# dac.net
KiCad netlist of a schematic drawn in Altium Designer
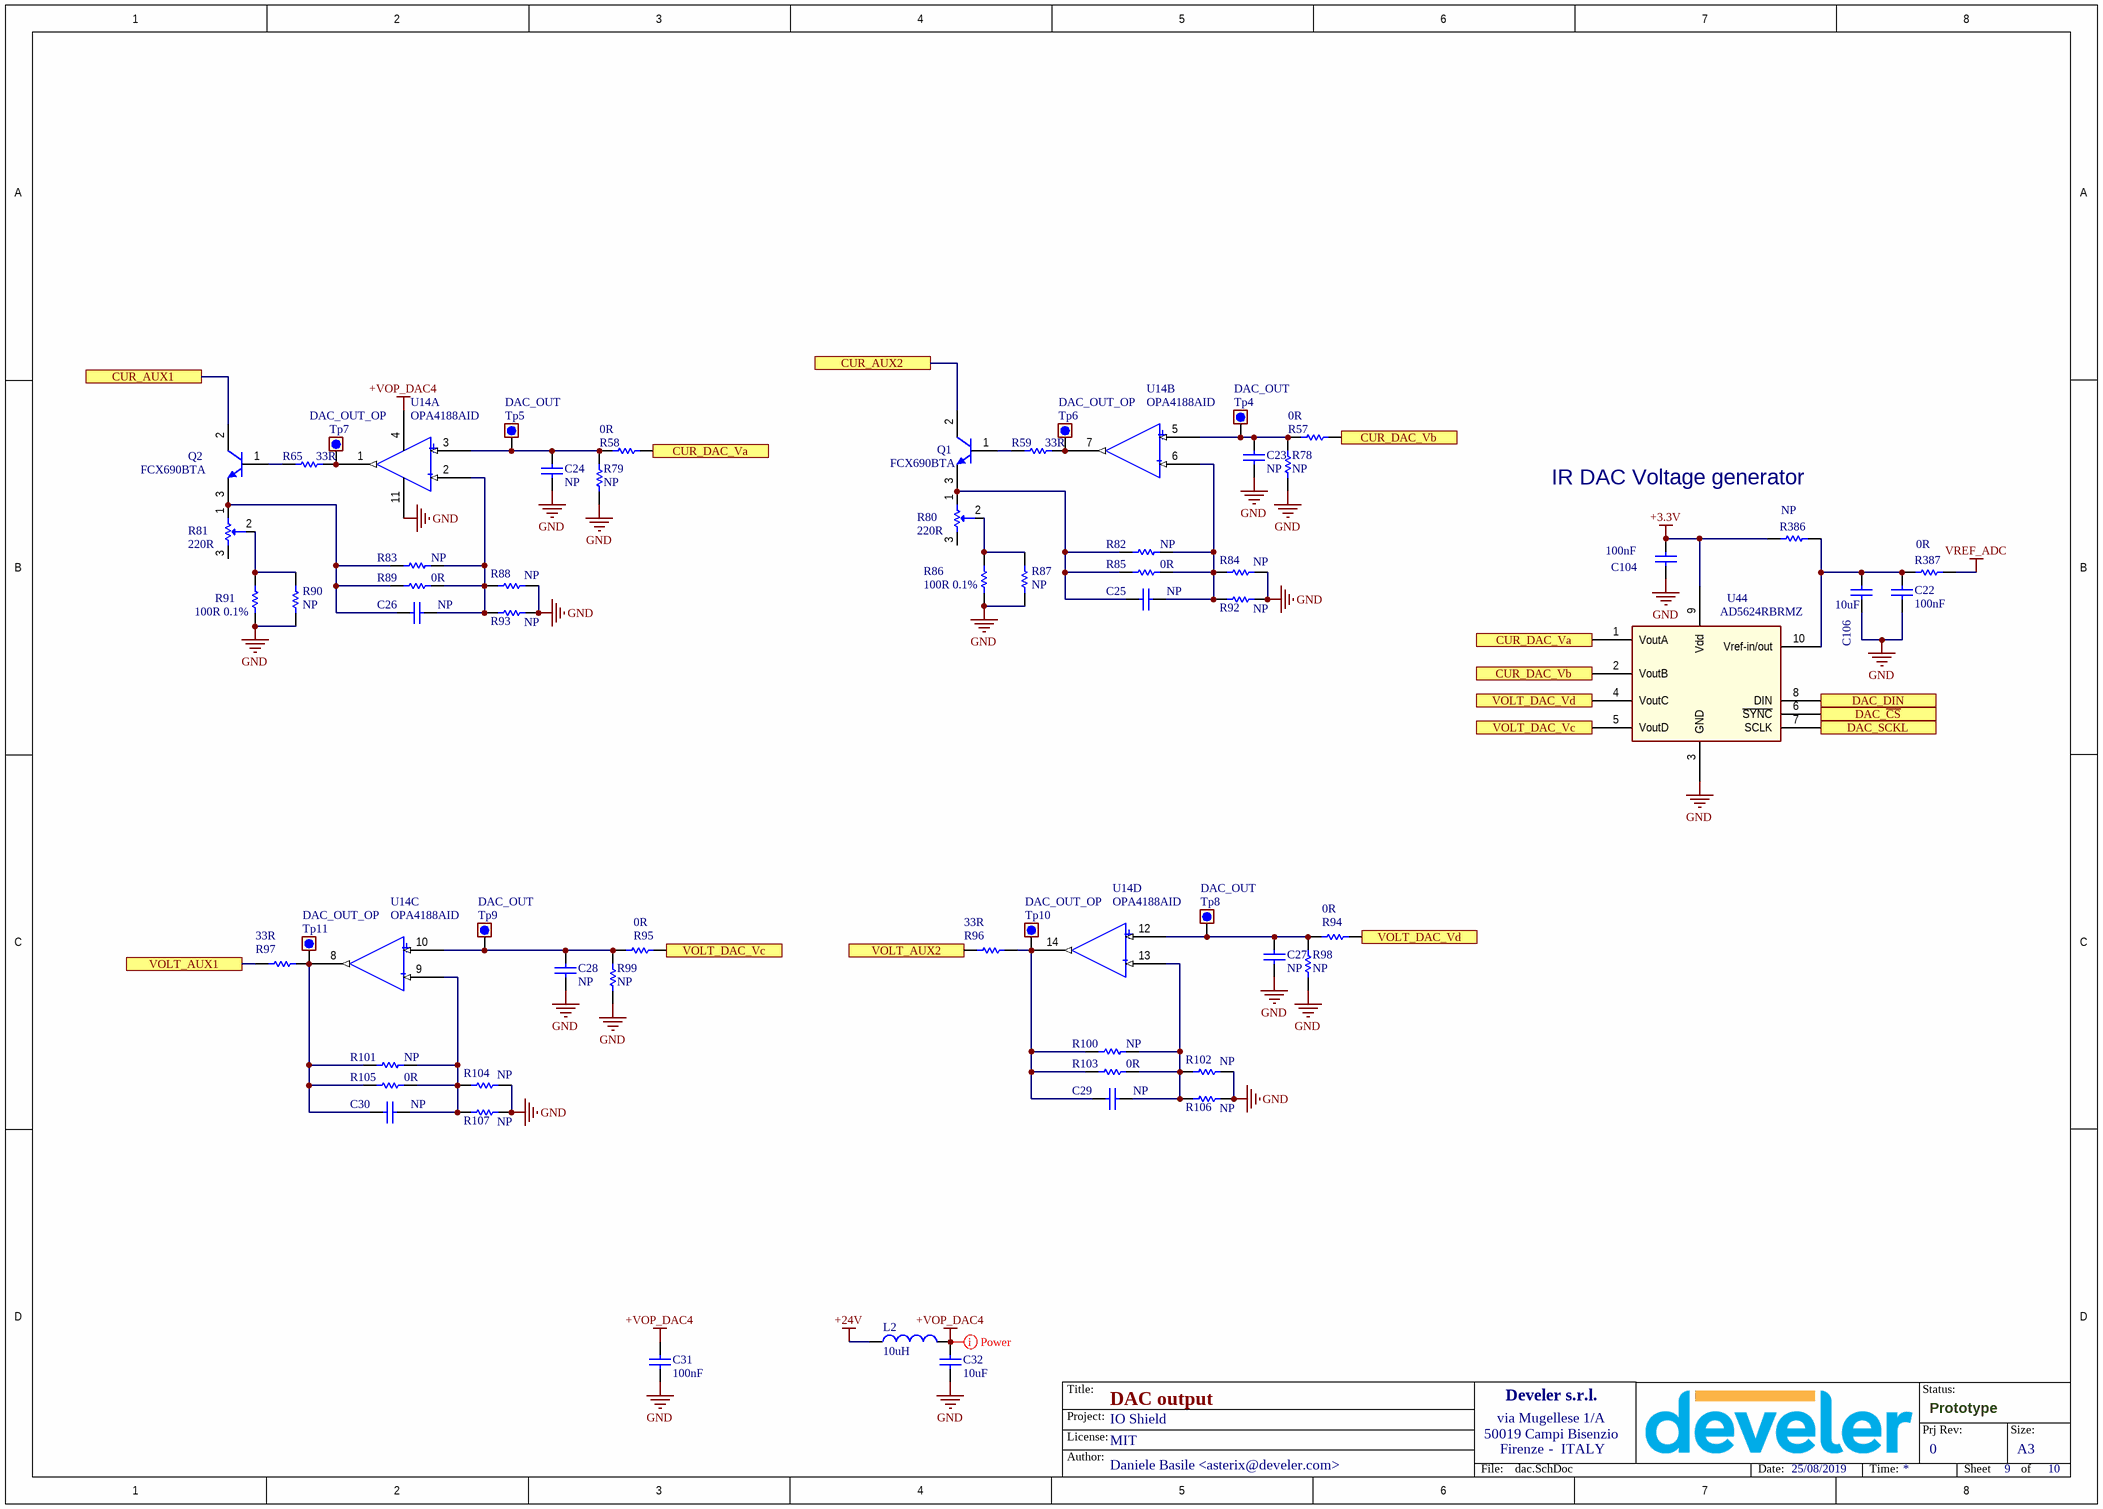
[diagram p0: dac.SchDoc]

(export (version "E")
  (design (tool "Eeschema 10.0.6"))
  (components
    (comp (ref "C22")
      (value "100nF")
      (footprint "0603_[1608]")
      (description "Ceramic X7R 50V")
      (fields (field (name "PUBLISHER") "Altium Limited"))
      (libsource (lib "DEVELER_Library") (part "Cap"))
    )
    (comp (ref "C23")
      (value "NP")
      (footprint "0603_[1608]")
      (description "Ceramic X7R 50V")
      (fields (field (name "PUBLISHER") "Altium Limited"))
      (libsource (lib "DEVELER_Library") (part "Cap"))
    )
    (comp (ref "C24")
      (value "NP")
      (footprint "0603_[1608]")
      (description "Ceramic X7R 50V")
      (fields (field (name "PUBLISHER") "Altium Limited"))
      (libsource (lib "DEVELER_Library") (part "Cap"))
    )
    (comp (ref "C25")
      (value "NP")
      (footprint "0603_[1608]")
      (description "Ceramic X7R 50V")
      (fields (field (name "PUBLISHER") "Altium Limited"))
      (libsource (lib "DEVELER_Library") (part "Cap"))
    )
    (comp (ref "C26")
      (value "NP")
      (footprint "0603_[1608]")
      (description "Ceramic X7R 50V")
      (fields (field (name "PUBLISHER") "Altium Limited"))
      (libsource (lib "DEVELER_Library") (part "Cap"))
    )
    (comp (ref "C27")
      (value "NP")
      (footprint "0603_[1608]")
      (description "Ceramic X7R 50V")
      (fields (field (name "PUBLISHER") "Altium Limited"))
      (libsource (lib "DEVELER_Library") (part "Cap"))
    )
    (comp (ref "C28")
      (value "NP")
      (footprint "0603_[1608]")
      (description "Ceramic X7R 50V")
      (fields (field (name "PUBLISHER") "Altium Limited"))
      (libsource (lib "DEVELER_Library") (part "Cap"))
    )
    (comp (ref "C29")
      (value "NP")
      (footprint "0603_[1608]")
      (description "Ceramic X7R 50V")
      (fields (field (name "PUBLISHER") "Altium Limited"))
      (libsource (lib "DEVELER_Library") (part "Cap"))
    )
    (comp (ref "C30")
      (value "NP")
      (footprint "0603_[1608]")
      (description "Ceramic X7R 50V")
      (fields (field (name "PUBLISHER") "Altium Limited"))
      (libsource (lib "DEVELER_Library") (part "Cap"))
    )
    (comp (ref "C31")
      (value "100nF")
      (footprint "0603_[1608]")
      (description "Ceramic X7R 50V")
      (fields (field (name "PUBLISHER") "Altium Limited"))
      (libsource (lib "DEVELER_Library") (part "Cap"))
    )
    (comp (ref "C32")
      (value "10uF")
      (footprint "1206_[3216]")
      (description "Ceramic X7R 25V")
      (fields (field (name "PUBLISHER") "Altium Limited"))
      (libsource (lib "DEVELER_Library") (part "Cap"))
    )
    (comp (ref "C104")
      (value "100nF")
      (footprint "0603_[1608]")
      (description "Ceramic X7R 50V")
      (fields (field (name "PUBLISHER") "Altium Limited"))
      (libsource (lib "DEVELER_Library") (part "Cap"))
    )
    (comp (ref "C106")
      (value "10uF")
      (footprint "1206_[3216]")
      (description "Ceramic X7R 25V")
      (fields (field (name "PUBLISHER") "Altium Limited"))
      (libsource (lib "DEVELER_Library") (part "Cap"))
    )
    (comp (ref "L2")
      (value "10uH")
      (footprint "1210_[3225]")
      (description "INDUCTOR, 1210 CASE, 10.0UH (ELJPA100KF)")
      (fields (field (name "PUBLISHER") "Altium Limited"))
      (libsource (lib "DEVELER_Library") (part "Inductor"))
    )
    (comp (ref "Q1")
      (value "FCX690BTA")
      (footprint "SOT-89")
      (description "NPN Bipolar Transistor")
      (fields (field (name "PUBLISHER") "Altium Limited"))
      (libsource (lib "Miscellaneous Devices") (part "NPN"))
    )
    (comp (ref "Q2")
      (value "FCX690BTA")
      (footprint "SOT-89")
      (description "NPN Bipolar Transistor")
      (fields (field (name "PUBLISHER") "Altium Limited"))
      (libsource (lib "Miscellaneous Devices") (part "NPN"))
    )
    (comp (ref "R57")
      (value "0R")
      (footprint "0603_[1608]")
      (description "Resistor")
      (libsource (lib "DEVELER_Library") (part "Res1"))
    )
    (comp (ref "R58")
      (value "0R")
      (footprint "0603_[1608]")
      (description "Resistor")
      (libsource (lib "DEVELER_Library") (part "Res1"))
    )
    (comp (ref "R59")
      (value "33R")
      (footprint "0603_[1608]")
      (description "Resistor")
      (libsource (lib "DEVELER_Library") (part "Res1"))
    )
    (comp (ref "R65")
      (value "33R")
      (footprint "0603_[1608]")
      (description "Resistor")
      (libsource (lib "DEVELER_Library") (part "Res1"))
    )
    (comp (ref "R78")
      (value "NP")
      (footprint "0603_[1608]")
      (description "Resistor")
      (libsource (lib "DEVELER_Library") (part "Res1"))
    )
    (comp (ref "R79")
      (value "NP")
      (footprint "0603_[1608]")
      (description "Resistor")
      (libsource (lib "DEVELER_Library") (part "Res1"))
    )
    (comp (ref "R80")
      (value "220R")
      (footprint "TRIMMER_THD_5x10MM_HORIZONTAL")
      (description "Trimmer 23 Turn 220ohm (T93YA221KT20;)")
      (libsource (lib "develer_library") (part "Trimmer_3p"))
    )
    (comp (ref "R81")
      (value "220R")
      (footprint "TRIMMER_THD_5x10MM_HORIZONTAL")
      (description "Trimmer 23 Turn 220ohm (T93YA221KT20;)")
      (libsource (lib "develer_library") (part "Trimmer_3p"))
    )
    (comp (ref "R82")
      (value "NP")
      (footprint "0603_[1608]")
      (description "Resistor")
      (libsource (lib "DEVELER_Library") (part "Res1"))
    )
    (comp (ref "R83")
      (value "NP")
      (footprint "0603_[1608]")
      (description "Resistor")
      (libsource (lib "DEVELER_Library") (part "Res1"))
    )
    (comp (ref "R84")
      (value "NP")
      (footprint "0603_[1608]")
      (description "Resistor")
      (libsource (lib "DEVELER_Library") (part "Res1"))
    )
    (comp (ref "R85")
      (value "0R")
      (footprint "0603_[1608]")
      (description "Resistor")
      (libsource (lib "DEVELER_Library") (part "Res1"))
    )
    (comp (ref "R86")
      (value "100R 0.1%")
      (footprint "0805_[2012]")
      (description "Resistor")
      (libsource (lib "DEVELER_Library") (part "Res1"))
    )
    (comp (ref "R87")
      (value "NP")
      (footprint "0805_[2012]")
      (description "Resistor")
      (libsource (lib "DEVELER_Library") (part "Res1"))
    )
    (comp (ref "R88")
      (value "NP")
      (footprint "0603_[1608]")
      (description "Resistor")
      (libsource (lib "DEVELER_Library") (part "Res1"))
    )
    (comp (ref "R89")
      (value "0R")
      (footprint "0603_[1608]")
      (description "Resistor")
      (libsource (lib "DEVELER_Library") (part "Res1"))
    )
    (comp (ref "R90")
      (value "NP")
      (footprint "0805_[2012]")
      (description "Resistor")
      (libsource (lib "DEVELER_Library") (part "Res1"))
    )
    (comp (ref "R91")
      (value "100R 0.1%")
      (footprint "0805_[2012]")
      (description "Resistor")
      (libsource (lib "DEVELER_Library") (part "Res1"))
    )
    (comp (ref "R92")
      (value "NP")
      (footprint "0603_[1608]")
      (description "Resistor")
      (libsource (lib "DEVELER_Library") (part "Res1"))
    )
    (comp (ref "R93")
      (value "NP")
      (footprint "0603_[1608]")
      (description "Resistor")
      (libsource (lib "DEVELER_Library") (part "Res1"))
    )
    (comp (ref "R94")
      (value "0R")
      (footprint "0603_[1608]")
      (description "Resistor")
      (libsource (lib "DEVELER_Library") (part "Res1"))
    )
    (comp (ref "R95")
      (value "0R")
      (footprint "0603_[1608]")
      (description "Resistor")
      (libsource (lib "DEVELER_Library") (part "Res1"))
    )
    (comp (ref "R96")
      (value "33R")
      (footprint "0603_[1608]")
      (description "Resistor")
      (libsource (lib "DEVELER_Library") (part "Res1"))
    )
    (comp (ref "R97")
      (value "33R")
      (footprint "0603_[1608]")
      (description "Resistor")
      (libsource (lib "DEVELER_Library") (part "Res1"))
    )
    (comp (ref "R98")
      (value "NP")
      (footprint "0603_[1608]")
      (description "Resistor")
      (libsource (lib "DEVELER_Library") (part "Res1"))
    )
    (comp (ref "R99")
      (value "NP")
      (footprint "0603_[1608]")
      (description "Resistor")
      (libsource (lib "DEVELER_Library") (part "Res1"))
    )
    (comp (ref "R100")
      (value "NP")
      (footprint "0603_[1608]")
      (description "Resistor")
      (libsource (lib "DEVELER_Library") (part "Res1"))
    )
    (comp (ref "R101")
      (value "NP")
      (footprint "0603_[1608]")
      (description "Resistor")
      (libsource (lib "DEVELER_Library") (part "Res1"))
    )
    (comp (ref "R102")
      (value "NP")
      (footprint "0603_[1608]")
      (description "Resistor")
      (libsource (lib "DEVELER_Library") (part "Res1"))
    )
    (comp (ref "R103")
      (value "0R")
      (footprint "0603_[1608]")
      (description "Resistor")
      (libsource (lib "DEVELER_Library") (part "Res1"))
    )
    (comp (ref "R104")
      (value "NP")
      (footprint "0603_[1608]")
      (description "Resistor")
      (libsource (lib "DEVELER_Library") (part "Res1"))
    )
    (comp (ref "R105")
      (value "0R")
      (footprint "0603_[1608]")
      (description "Resistor")
      (libsource (lib "DEVELER_Library") (part "Res1"))
    )
    (comp (ref "R106")
      (value "NP")
      (footprint "0603_[1608]")
      (description "Resistor")
      (libsource (lib "DEVELER_Library") (part "Res1"))
    )
    (comp (ref "R107")
      (value "NP")
      (footprint "0603_[1608]")
      (description "Resistor")
      (libsource (lib "DEVELER_Library") (part "Res1"))
    )
    (comp (ref "R386")
      (value "NP")
      (footprint "0603_[1608]")
      (description "Resistor")
      (libsource (lib "DEVELER_Library") (part "Res1"))
    )
    (comp (ref "R387")
      (value "0R")
      (footprint "0603_[1608]")
      (description "Resistor")
      (libsource (lib "DEVELER_Library") (part "Res1"))
    )
    (comp (ref "Tp4")
      (value "DAC_OUT")
      (footprint "TEST_POINT_THD_D1.6MM")
      (description "Test point")
      (libsource (lib "DEVELER_Library") (part "Test_point"))
    )
    (comp (ref "Tp5")
      (value "DAC_OUT")
      (footprint "TEST_POINT_THD_D1.6MM")
      (description "Test point")
      (libsource (lib "DEVELER_Library") (part "Test_point"))
    )
    (comp (ref "Tp6")
      (value "DAC_OUT_OP")
      (footprint "TEST_POINT_THD_D1.6MM")
      (description "Test point")
      (libsource (lib "DEVELER_Library") (part "Test_point"))
    )
    (comp (ref "Tp7")
      (value "DAC_OUT_OP")
      (footprint "TEST_POINT_THD_D1.6MM")
      (description "Test point")
      (libsource (lib "DEVELER_Library") (part "Test_point"))
    )
    (comp (ref "Tp8")
      (value "DAC_OUT")
      (footprint "TEST_POINT_THD_D1.6MM")
      (description "Test point")
      (libsource (lib "DEVELER_Library") (part "Test_point"))
    )
    (comp (ref "Tp9")
      (value "DAC_OUT")
      (footprint "TEST_POINT_THD_D1.6MM")
      (description "Test point")
      (libsource (lib "DEVELER_Library") (part "Test_point"))
    )
    (comp (ref "Tp10")
      (value "DAC_OUT_OP")
      (footprint "TEST_POINT_THD_D1.6MM")
      (description "Test point")
      (libsource (lib "DEVELER_Library") (part "Test_point"))
    )
    (comp (ref "Tp11")
      (value "DAC_OUT_OP")
      (footprint "TEST_POINT_THD_D1.6MM")
      (description "Test point")
      (libsource (lib "DEVELER_Library") (part "Test_point"))
    )
    (comp (ref "U14")
      (value "OPA4188AID")
      (footprint "SOIC14")
      (description "Quad Op Amp")
      (libsource (lib "") (part "OpAmp_1"))
    )
    (comp (ref "U44")
      (value "AD5624RBRMZ")
      (footprint "MSOP50P490X110-10P")
      (description "12bit DAC")
      (libsource (lib "DEVELER_Library") (part "AD5624R_BRMZ_MSOP"))
    )
  )
  (nets
    (net (code "1") (name "+3.3V") (class "Default")
      (node (ref "C104") (pin "2") (pinfunction "2_2") (pintype "passive"))
      (node (ref "R386") (pin "2") (pinfunction "2_2") (pintype "passive"))
      (node (ref "U44") (pin "9") (pinfunction "Vdd_9") (pintype "passive"))
    )
    (net (code "2") (name "+24V") (class "Default")
      (node (ref "L2") (pin "1") (pinfunction "1_1") (pintype "passive"))
    )
    (net (code "3") (name "+VOP_DAC4") (class "Default")
      (node (ref "C31") (pin "1") (pinfunction "1_1") (pintype "passive"))
      (node (ref "C32") (pin "2") (pinfunction "2_2") (pintype "passive"))
      (node (ref "L2") (pin "2") (pinfunction "2_2") (pintype "passive"))
      (node (ref "U14") (pin "4") (pinfunction "V+_4") (pintype "power_in"))
    )
    (net (code "4") (name "/CUR_AUX1") (class "Default")
      (node (ref "Q2") (pin "2") (pinfunction "C_2") (pintype "passive"))
    )
    (net (code "5") (name "/CUR_AUX2") (class "Default")
      (node (ref "Q1") (pin "2") (pinfunction "C_2") (pintype "passive"))
    )
    (net (code "6") (name "/CUR_DAC_Va") (class "Default")
      (node (ref "R58") (pin "1") (pinfunction "1_1") (pintype "passive"))
      (node (ref "U44") (pin "1") (pinfunction "VoutA_1") (pintype "passive"))
    )
    (net (code "7") (name "/CUR_DAC_Vb") (class "Default")
      (node (ref "R57") (pin "1") (pinfunction "1_1") (pintype "passive"))
      (node (ref "U44") (pin "2") (pinfunction "VoutB_2") (pintype "passive"))
    )
    (net (code "8") (name "/DAC_DIN") (class "Default")
      (node (ref "U44") (pin "8") (pinfunction "DIN_8") (pintype "passive"))
    )
    (net (code "9") (name "/DAC_SCKL") (class "Default")
      (node (ref "U44") (pin "7") (pinfunction "SCLK_7") (pintype "passive"))
    )
    (net (code "10") (name "/DAC_~{CS}") (class "Default")
      (node (ref "U44") (pin "6") (pinfunction "~{SYNC}_6") (pintype "passive"))
    )
    (net (code "11") (name "/VOLT_AUX1") (class "Default")
      (node (ref "R97") (pin "1") (pinfunction "1_1") (pintype "passive"))
    )
    (net (code "12") (name "/VOLT_AUX2") (class "Default")
      (node (ref "R96") (pin "1") (pinfunction "1_1") (pintype "passive"))
    )
    (net (code "13") (name "/VOLT_DAC_Vc") (class "Default")
      (node (ref "R95") (pin "1") (pinfunction "1_1") (pintype "passive"))
      (node (ref "U44") (pin "5") (pinfunction "VoutD_5") (pintype "passive"))
    )
    (net (code "14") (name "/VOLT_DAC_Vd") (class "Default")
      (node (ref "R94") (pin "1") (pinfunction "1_1") (pintype "passive"))
      (node (ref "U44") (pin "4") (pinfunction "VoutC_4") (pintype "passive"))
    )
    (net (code "15") (name "GND") (class "Default")
      (node (ref "C104") (pin "1") (pinfunction "1_1") (pintype "passive"))
      (node (ref "C106") (pin "1") (pinfunction "1_1") (pintype "passive"))
      (node (ref "C22") (pin "2") (pinfunction "2_2") (pintype "passive"))
      (node (ref "C23") (pin "2") (pinfunction "2_2") (pintype "passive"))
      (node (ref "C24") (pin "2") (pinfunction "2_2") (pintype "passive"))
      (node (ref "C27") (pin "2") (pinfunction "2_2") (pintype "passive"))
      (node (ref "C28") (pin "2") (pinfunction "2_2") (pintype "passive"))
      (node (ref "C31") (pin "2") (pinfunction "2_2") (pintype "passive"))
      (node (ref "C32") (pin "1") (pinfunction "1_1") (pintype "passive"))
      (node (ref "R102") (pin "2") (pinfunction "2_2") (pintype "passive"))
      (node (ref "R104") (pin "2") (pinfunction "2_2") (pintype "passive"))
      (node (ref "R106") (pin "2") (pinfunction "2_2") (pintype "passive"))
      (node (ref "R107") (pin "2") (pinfunction "2_2") (pintype "passive"))
      (node (ref "R78") (pin "2") (pinfunction "2_2") (pintype "passive"))
      (node (ref "R79") (pin "2") (pinfunction "2_2") (pintype "passive"))
      (node (ref "R84") (pin "2") (pinfunction "2_2") (pintype "passive"))
      (node (ref "R86") (pin "1") (pinfunction "1_1") (pintype "passive"))
      (node (ref "R87") (pin "1") (pinfunction "1_1") (pintype "passive"))
      (node (ref "R88") (pin "2") (pinfunction "2_2") (pintype "passive"))
      (node (ref "R90") (pin "1") (pinfunction "1_1") (pintype "passive"))
      (node (ref "R91") (pin "1") (pinfunction "1_1") (pintype "passive"))
      (node (ref "R92") (pin "2") (pinfunction "2_2") (pintype "passive"))
      (node (ref "R93") (pin "2") (pinfunction "2_2") (pintype "passive"))
      (node (ref "R98") (pin "2") (pinfunction "2_2") (pintype "passive"))
      (node (ref "R99") (pin "2") (pinfunction "2_2") (pintype "passive"))
      (node (ref "U14") (pin "11") (pinfunction "V-_11") (pintype "power_in"))
      (node (ref "U44") (pin "3") (pinfunction "GND_3") (pintype "passive"))
    )
    (net (code "16") (name "Net-(Q1-B)") (class "Default")
      (node (ref "Q1") (pin "1") (pinfunction "B_1") (pintype "passive"))
      (node (ref "R59") (pin "1") (pinfunction "1_1") (pintype "passive"))
    )
    (net (code "17") (name "Net-(Q1-E)") (class "Default")
      (node (ref "C25") (pin "2") (pinfunction "2_2") (pintype "passive"))
      (node (ref "Q1") (pin "3") (pinfunction "E_3") (pintype "passive"))
      (node (ref "R80") (pin "1") (pinfunction "1_1") (pintype "passive"))
      (node (ref "R82") (pin "1") (pinfunction "1_1") (pintype "passive"))
      (node (ref "R85") (pin "1") (pinfunction "1_1") (pintype "passive"))
    )
    (net (code "18") (name "Net-(Q2-B)") (class "Default")
      (node (ref "Q2") (pin "1") (pinfunction "B_1") (pintype "passive"))
      (node (ref "R65") (pin "1") (pinfunction "1_1") (pintype "passive"))
    )
    (net (code "19") (name "Net-(Q2-E)") (class "Default")
      (node (ref "C26") (pin "2") (pinfunction "2_2") (pintype "passive"))
      (node (ref "Q2") (pin "3") (pinfunction "E_3") (pintype "passive"))
      (node (ref "R81") (pin "1") (pinfunction "1_1") (pintype "passive"))
      (node (ref "R83") (pin "1") (pinfunction "1_1") (pintype "passive"))
      (node (ref "R89") (pin "1") (pinfunction "1_1") (pintype "passive"))
    )
    (net (code "20") (name "Net-(R80-Pad2)") (class "Default")
      (node (ref "R80") (pin "2") (pinfunction "2_2") (pintype "passive"))
      (node (ref "R86") (pin "2") (pinfunction "2_2") (pintype "passive"))
      (node (ref "R87") (pin "2") (pinfunction "2_2") (pintype "passive"))
    )
    (net (code "21") (name "Net-(R81-Pad2)") (class "Default")
      (node (ref "R81") (pin "2") (pinfunction "2_2") (pintype "passive"))
      (node (ref "R90") (pin "2") (pinfunction "2_2") (pintype "passive"))
      (node (ref "R91") (pin "2") (pinfunction "2_2") (pintype "passive"))
    )
    (net (code "22") (name "Net-(U14A-IN+)") (class "Default")
      (node (ref "C24") (pin "1") (pinfunction "1_1") (pintype "passive"))
      (node (ref "R58") (pin "2") (pinfunction "2_2") (pintype "passive"))
      (node (ref "R79") (pin "1") (pinfunction "1_1") (pintype "passive"))
      (node (ref "Tp5") (pin "1") (pinfunction "1_1") (pintype "passive"))
      (node (ref "U14") (pin "3") (pinfunction "IN+_3") (pintype "input"))
    )
    (net (code "23") (name "Net-(U14A-IN-)") (class "Default")
      (node (ref "C26") (pin "1") (pinfunction "1_1") (pintype "passive"))
      (node (ref "R83") (pin "2") (pinfunction "2_2") (pintype "passive"))
      (node (ref "R88") (pin "1") (pinfunction "1_1") (pintype "passive"))
      (node (ref "R89") (pin "2") (pinfunction "2_2") (pintype "passive"))
      (node (ref "R93") (pin "1") (pinfunction "1_1") (pintype "passive"))
      (node (ref "U14") (pin "2") (pinfunction "IN-_2") (pintype "input"))
    )
    (net (code "24") (name "Net-(U14A-OUT)") (class "Default")
      (node (ref "R65") (pin "2") (pinfunction "2_2") (pintype "passive"))
      (node (ref "Tp7") (pin "1") (pinfunction "1_1") (pintype "passive"))
      (node (ref "U14") (pin "1") (pinfunction "OUT_1") (pintype "output"))
    )
    (net (code "25") (name "Net-(U14B-IN+)") (class "Default")
      (node (ref "C23") (pin "1") (pinfunction "1_1") (pintype "passive"))
      (node (ref "R57") (pin "2") (pinfunction "2_2") (pintype "passive"))
      (node (ref "R78") (pin "1") (pinfunction "1_1") (pintype "passive"))
      (node (ref "Tp4") (pin "1") (pinfunction "1_1") (pintype "passive"))
      (node (ref "U14") (pin "5") (pinfunction "IN+_5") (pintype "input"))
    )
    (net (code "26") (name "Net-(U14B-IN-)") (class "Default")
      (node (ref "C25") (pin "1") (pinfunction "1_1") (pintype "passive"))
      (node (ref "R82") (pin "2") (pinfunction "2_2") (pintype "passive"))
      (node (ref "R84") (pin "1") (pinfunction "1_1") (pintype "passive"))
      (node (ref "R85") (pin "2") (pinfunction "2_2") (pintype "passive"))
      (node (ref "R92") (pin "1") (pinfunction "1_1") (pintype "passive"))
      (node (ref "U14") (pin "6") (pinfunction "IN-_6") (pintype "input"))
    )
    (net (code "27") (name "Net-(U14B-OUT)") (class "Default")
      (node (ref "R59") (pin "2") (pinfunction "2_2") (pintype "passive"))
      (node (ref "Tp6") (pin "1") (pinfunction "1_1") (pintype "passive"))
      (node (ref "U14") (pin "7") (pinfunction "OUT_7") (pintype "output"))
    )
    (net (code "28") (name "Net-(U14C-IN+)") (class "Default")
      (node (ref "C28") (pin "1") (pinfunction "1_1") (pintype "passive"))
      (node (ref "R95") (pin "2") (pinfunction "2_2") (pintype "passive"))
      (node (ref "R99") (pin "1") (pinfunction "1_1") (pintype "passive"))
      (node (ref "Tp9") (pin "1") (pinfunction "1_1") (pintype "passive"))
      (node (ref "U14") (pin "10") (pinfunction "IN+_10") (pintype "input"))
    )
    (net (code "29") (name "Net-(U14C-IN-)") (class "Default")
      (node (ref "C30") (pin "1") (pinfunction "1_1") (pintype "passive"))
      (node (ref "R101") (pin "2") (pinfunction "2_2") (pintype "passive"))
      (node (ref "R104") (pin "1") (pinfunction "1_1") (pintype "passive"))
      (node (ref "R105") (pin "2") (pinfunction "2_2") (pintype "passive"))
      (node (ref "R107") (pin "1") (pinfunction "1_1") (pintype "passive"))
      (node (ref "U14") (pin "9") (pinfunction "IN-_9") (pintype "input"))
    )
    (net (code "30") (name "Net-(U14C-OUT)") (class "Default")
      (node (ref "C30") (pin "2") (pinfunction "2_2") (pintype "passive"))
      (node (ref "R101") (pin "1") (pinfunction "1_1") (pintype "passive"))
      (node (ref "R105") (pin "1") (pinfunction "1_1") (pintype "passive"))
      (node (ref "R97") (pin "2") (pinfunction "2_2") (pintype "passive"))
      (node (ref "Tp11") (pin "1") (pinfunction "1_1") (pintype "passive"))
      (node (ref "U14") (pin "8") (pinfunction "OUT_8") (pintype "output"))
    )
    (net (code "31") (name "Net-(U14D-IN+)") (class "Default")
      (node (ref "C27") (pin "1") (pinfunction "1_1") (pintype "passive"))
      (node (ref "R94") (pin "2") (pinfunction "2_2") (pintype "passive"))
      (node (ref "R98") (pin "1") (pinfunction "1_1") (pintype "passive"))
      (node (ref "Tp8") (pin "1") (pinfunction "1_1") (pintype "passive"))
      (node (ref "U14") (pin "12") (pinfunction "IN+_12") (pintype "input"))
    )
    (net (code "32") (name "Net-(U14D-IN-)") (class "Default")
      (node (ref "C29") (pin "1") (pinfunction "1_1") (pintype "passive"))
      (node (ref "R100") (pin "2") (pinfunction "2_2") (pintype "passive"))
      (node (ref "R102") (pin "1") (pinfunction "1_1") (pintype "passive"))
      (node (ref "R103") (pin "2") (pinfunction "2_2") (pintype "passive"))
      (node (ref "R106") (pin "1") (pinfunction "1_1") (pintype "passive"))
      (node (ref "U14") (pin "13") (pinfunction "IN-_13") (pintype "input"))
    )
    (net (code "33") (name "Net-(U14D-OUT)") (class "Default")
      (node (ref "C29") (pin "2") (pinfunction "2_2") (pintype "passive"))
      (node (ref "R100") (pin "1") (pinfunction "1_1") (pintype "passive"))
      (node (ref "R103") (pin "1") (pinfunction "1_1") (pintype "passive"))
      (node (ref "R96") (pin "2") (pinfunction "2_2") (pintype "passive"))
      (node (ref "Tp10") (pin "1") (pinfunction "1_1") (pintype "passive"))
      (node (ref "U14") (pin "14") (pinfunction "OUT_14") (pintype "output"))
    )
    (net (code "34") (name "Net-(U44-Vref-in{slash}out)") (class "Default")
      (node (ref "C106") (pin "2") (pinfunction "2_2") (pintype "passive"))
      (node (ref "C22") (pin "1") (pinfunction "1_1") (pintype "passive"))
      (node (ref "R386") (pin "1") (pinfunction "1_1") (pintype "passive"))
      (node (ref "R387") (pin "2") (pinfunction "2_2") (pintype "passive"))
      (node (ref "U44") (pin "10") (pinfunction "Vref-in/out_10") (pintype "passive"))
    )
    (net (code "35") (name "VREF_ADC") (class "Default")
      (node (ref "R387") (pin "1") (pinfunction "1_1") (pintype "passive"))
    )
    (net (code "36") (name "unconnected-(R80-Pad3)") (class "Default")
      (node (ref "R80") (pin "3") (pinfunction "3_3") (pintype "passive"))
    )
    (net (code "37") (name "unconnected-(R81-Pad3)") (class "Default")
      (node (ref "R81") (pin "3") (pinfunction "3_3") (pintype "passive"))
    )
  )
)
